# Ethernet_SD.net
KiCad netlist of a schematic drawn in Altium Designer
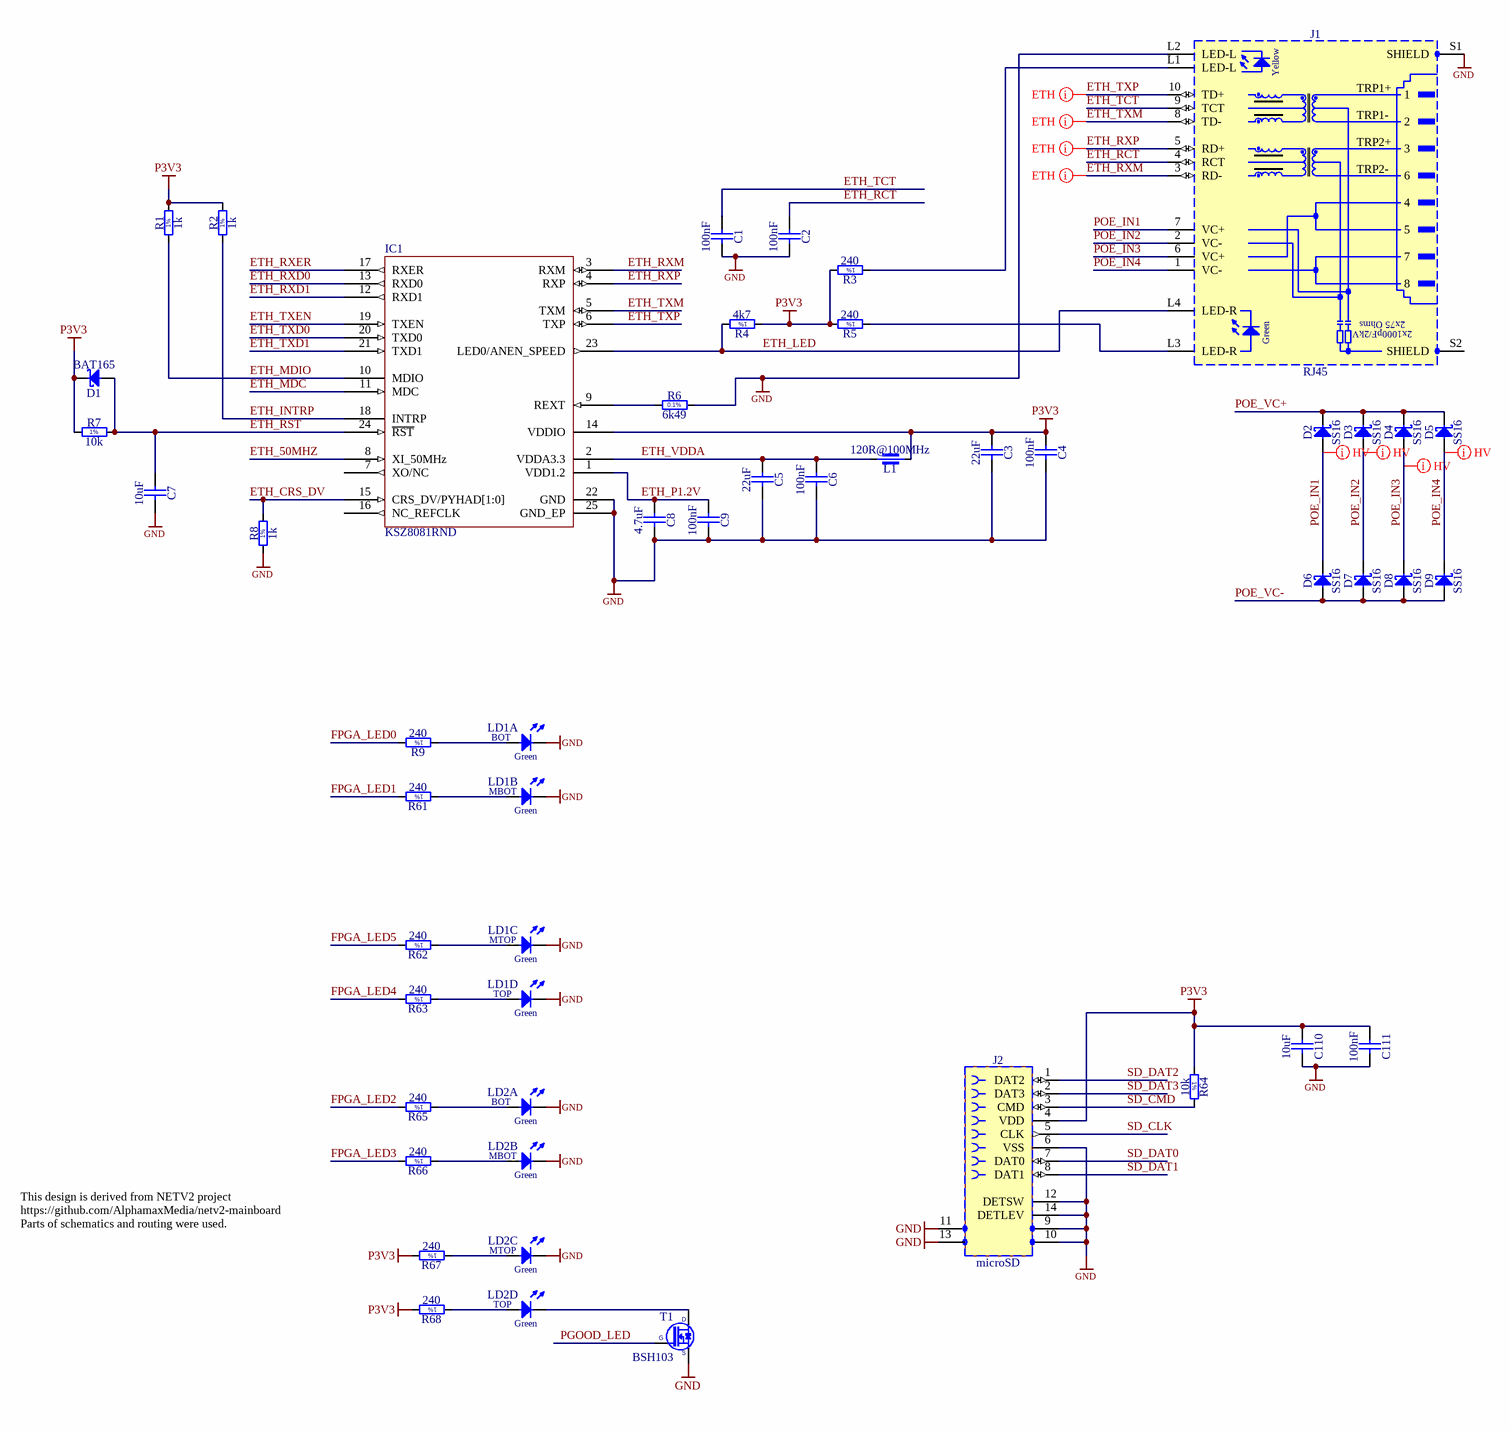
[diagram p0: Ethernet_SD.SchDoc]

(export (version "E")
  (design (tool "Eeschema 10.0.6"))
  (components
    (comp (ref "C1")
      (value "100nF")
      (footprint "CAPC2012X135N")
      (description "Non-polarised capacitor")
      (fields
        (field (name "PART NUMBER") "CC0805_100NF_50V_10%_X7R")
        (field (name "VOLTAGE") "50V")
        (field (name "AUTHOR") "CERN DEM JLC")
      )
      (libsource (lib "Capacitors") (part "Capacitor - non polarized"))
    )
    (comp (ref "C2")
      (value "100nF")
      (footprint "CAPC2012X135N")
      (description "Non-polarised capacitor")
      (fields
        (field (name "PART NUMBER") "CC0805_100NF_50V_10%_X7R")
        (field (name "VOLTAGE") "50V")
        (field (name "AUTHOR") "CERN DEM JLC")
      )
      (libsource (lib "Capacitors") (part "Capacitor - non polarized"))
    )
    (comp (ref "C3")
      (value "22uF")
      (footprint "CAPC2012X135N")
      (description "Non-polarised capacitor")
      (fields
        (field (name "PART NUMBER") "CC0805_22UF_16V_10%_X5R")
        (field (name "VOLTAGE") "16V")
        (field (name "AUTHOR") "CERN DEM JLC")
      )
      (libsource (lib "Capacitors") (part "Capacitor - non polarized"))
    )
    (comp (ref "C4")
      (value "100nF")
      (footprint "CAPC0603X33N")
      (description "Non-polarised capacitor")
      (fields
        (field (name "PART NUMBER") "CC0201_100NF_6.3V_10%_X5R")
        (field (name "VOLTAGE") "6.3V")
        (field (name "AUTHOR") "CERN DEM JLC")
      )
      (libsource (lib "Capacitors") (part "Capacitor - non polarized"))
    )
    (comp (ref "C5")
      (value "22uF")
      (footprint "CAPC2012X135N")
      (description "Non-polarised capacitor")
      (fields
        (field (name "PART NUMBER") "CC0805_22UF_16V_10%_X5R")
        (field (name "VOLTAGE") "16V")
        (field (name "AUTHOR") "CERN DEM JLC")
      )
      (libsource (lib "Capacitors") (part "Capacitor - non polarized"))
    )
    (comp (ref "C6")
      (value "100nF")
      (footprint "CAPC0603X33N")
      (description "Non-polarised capacitor")
      (fields
        (field (name "PART NUMBER") "CC0201_100NF_6.3V_10%_X5R")
        (field (name "VOLTAGE") "6.3V")
        (field (name "AUTHOR") "CERN DEM JLC")
      )
      (libsource (lib "Capacitors") (part "Capacitor - non polarized"))
    )
    (comp (ref "C7")
      (value "10uF")
      (footprint "CAPC1608X80N")
      (description "Non-polarised capacitor")
      (fields
        (field (name "PART NUMBER") "CC0603_10UF_10V_10%_X5R")
        (field (name "VOLTAGE") "10V")
        (field (name "AUTHOR") "CERN DEM JLC")
      )
      (libsource (lib "Capacitors") (part "Capacitor - non polarized"))
    )
    (comp (ref "C8")
      (value "4.7uF")
      (footprint "CAPC1005X55N")
      (description "Non-polarised capacitor")
      (fields
        (field (name "PART NUMBER") "CC0402_4.7UF_6.3V_20%_X5R")
        (field (name "VOLTAGE") "6.3V")
        (field (name "AUTHOR") "CERN DEM JLC")
      )
      (libsource (lib "Capacitors") (part "Capacitor - non polarized"))
    )
    (comp (ref "C9")
      (value "100nF")
      (footprint "CAPC0603X33N")
      (description "Non-polarised capacitor")
      (fields
        (field (name "PART NUMBER") "CC0201_100NF_6.3V_10%_X5R")
        (field (name "VOLTAGE") "6.3V")
        (field (name "AUTHOR") "CERN DEM JLC")
      )
      (libsource (lib "Capacitors") (part "Capacitor - non polarized"))
    )
    (comp (ref "C110")
      (value "10uF")
      (footprint "CAPC1608X80N")
      (description "Non-polarised capacitor")
      (fields
        (field (name "PART NUMBER") "CC0603_10UF_10V_10%_X5R")
        (field (name "VOLTAGE") "10V")
        (field (name "AUTHOR") "CERN DEM JLC")
      )
      (libsource (lib "Capacitors") (part "Capacitor - non polarized"))
    )
    (comp (ref "C111")
      (value "100nF")
      (footprint "CAPC0603X33N")
      (description "Non-polarised capacitor")
      (fields
        (field (name "PART NUMBER") "CC0201_100NF_6.3V_10%_X5R")
        (field (name "VOLTAGE") "6.3V")
        (field (name "AUTHOR") "CERN DEM JLC")
      )
      (libsource (lib "Capacitors") (part "Capacitor - non polarized"))
    )
    (comp (ref "D1")
      (value "BAT165")
      (footprint "SOD2512X110N")
      (description "Schottky Diode")
      (fields
        (field (name "VOLTAGE") "40V")
        (field (name "POWER") "750mA")
        (field (name "AUTHOR") "CERN DEM JLC")
      )
      (libsource (lib "ICs And Semiconductors") (part "Diode Schottky"))
    )
    (comp (ref "D2")
      (value "SS16")
      (footprint "DIOM5127X229N")
      (description "Schottky Diode")
      (fields
        (field (name "VOLTAGE") "60V")
        (field (name "POWER") "1A")
        (field (name "AUTHOR") "CERN DEM JLC")
      )
      (libsource (lib "ICs And Semiconductors") (part "Diode Schottky"))
    )
    (comp (ref "D3")
      (value "SS16")
      (footprint "DIOM5127X229N")
      (description "Schottky Diode")
      (fields
        (field (name "VOLTAGE") "60V")
        (field (name "POWER") "1A")
        (field (name "AUTHOR") "CERN DEM JLC")
      )
      (libsource (lib "ICs And Semiconductors") (part "Diode Schottky"))
    )
    (comp (ref "D4")
      (value "SS16")
      (footprint "DIOM5127X229N")
      (description "Schottky Diode")
      (fields
        (field (name "VOLTAGE") "60V")
        (field (name "POWER") "1A")
        (field (name "AUTHOR") "CERN DEM JLC")
      )
      (libsource (lib "ICs And Semiconductors") (part "Diode Schottky"))
    )
    (comp (ref "D5")
      (value "SS16")
      (footprint "DIOM5127X229N")
      (description "Schottky Diode")
      (fields
        (field (name "VOLTAGE") "60V")
        (field (name "POWER") "1A")
        (field (name "AUTHOR") "CERN DEM JLC")
      )
      (libsource (lib "ICs And Semiconductors") (part "Diode Schottky"))
    )
    (comp (ref "D6")
      (value "SS16")
      (footprint "DIOM5127X229N")
      (description "Schottky Diode")
      (fields
        (field (name "VOLTAGE") "60V")
        (field (name "POWER") "1A")
        (field (name "AUTHOR") "CERN DEM JLC")
      )
      (libsource (lib "ICs And Semiconductors") (part "Diode Schottky"))
    )
    (comp (ref "D7")
      (value "SS16")
      (footprint "DIOM5127X229N")
      (description "Schottky Diode")
      (fields
        (field (name "VOLTAGE") "60V")
        (field (name "POWER") "1A")
        (field (name "AUTHOR") "CERN DEM JLC")
      )
      (libsource (lib "ICs And Semiconductors") (part "Diode Schottky"))
    )
    (comp (ref "D8")
      (value "SS16")
      (footprint "DIOM5127X229N")
      (description "Schottky Diode")
      (fields
        (field (name "VOLTAGE") "60V")
        (field (name "POWER") "1A")
        (field (name "AUTHOR") "CERN DEM JLC")
      )
      (libsource (lib "ICs And Semiconductors") (part "Diode Schottky"))
    )
    (comp (ref "D9")
      (value "SS16")
      (footprint "DIOM5127X229N")
      (description "Schottky Diode")
      (fields
        (field (name "VOLTAGE") "60V")
        (field (name "POWER") "1A")
        (field (name "AUTHOR") "CERN DEM JLC")
      )
      (libsource (lib "ICs And Semiconductors") (part "Diode Schottky"))
    )
    (comp (ref "IC1")
      (value "KSZ8081RND")
      (footprint "QFN50P400X400-24VBN")
      (description "KSZ8081RND MII Ethernet PHY")
      (fields (field (name "MPN") "KSZ8081RNDCA"))
      (libsource (lib "commonsch-new") (part "KSZ8081RND"))
    )
    (comp (ref "J1")
      (value "RJ45")
      (footprint "ABRACON_ARJM11C7-114-BA-EW2")
      (description "MagJack 10/100BaseT, PoE+, 1X1, OG/Y, -40 to 85*C, Tab Up, RoHS")
      (fields
        (field (name "PART NUMBER") "ARJM11C7-114-BA-EW2")
        (field (name "MANUFACTURER") "Abracon")
        (field (name "AUTHOR") "GK")
      )
      (libsource (lib "LIBRARY_SCH") (part "CON_ETH_POE_ARJM11C7"))
    )
    (comp (ref "J2")
      (value "microSD")
      (footprint "MOLEX_502570-0893")
      (description "Connector MicroSD 8 Pin")
      (fields
        (field (name "PART NUMBER") "MOLEX_502570-0893")
        (field (name "MANUFACTURER") "MOLEX")
        (field (name "AUTHOR") "CERN DEM JLC")
      )
      (libsource (lib "Connectors") (part "MOLEX_502570-0893"))
    )
    (comp (ref "L1")
      (value "120R@100MHz")
      (footprint "INDC1608X65N")
      (fields
        (field (name "PART NUMBER") "IND0603_MURATA_BLM18SG121TN1D")
        (field (name "POWER") "3A")
        (field (name "TOLERANCE") "±25%")
        (field (name "AUTHOR") "CERN DEM JLC")
      )
      (libsource (lib "Inductors & Transformers") (part "Ferrite Bead"))
    )
    (comp (ref "LD1")
      (value "Green")
      (footprint "LED_BIVAR_H485CGDL")
      (description "LED x4 Green 1C2A-BOT_3C4A_5C6A_7C8A-TOP")
      (fields
        (field (name "PART NUMBER") "LED_BIVAR_H485CGDL")
        (field (name "MANUFACTURER") "BIVAR")
        (field (name "AUTHOR") "CERN DEM JLC")
      )
      (libsource (lib "ICs And Semiconductors") (part "LED x4 Green 1C2A-BOT_3C4A_5C6A_7C8A-TOP"))
    )
    (comp (ref "LD2")
      (value "Green")
      (footprint "LED_BIVAR_H485CGDL")
      (description "LED x4 Green 1C2A-BOT_3C4A_5C6A_7C8A-TOP")
      (fields
        (field (name "PART NUMBER") "LED_BIVAR_H485CGDL")
        (field (name "MANUFACTURER") "BIVAR")
        (field (name "AUTHOR") "CERN DEM JLC")
      )
      (libsource (lib "ICs And Semiconductors") (part "LED x4 Green 1C2A-BOT_3C4A_5C6A_7C8A-TOP"))
    )
    (comp (ref "R1")
      (value "1k")
      (footprint "RESC1005X40N")
      (description "Resistor - 1%")
      (fields
        (field (name "PART NUMBER") "R0402_1K_1%_0.0625W_100PPM")
        (field (name "POWER") "0.0625W")
        (field (name "AUTHOR") "CERN DEM JLC")
      )
      (libsource (lib "Resistors") (part "Resistor - 1%"))
    )
    (comp (ref "R2")
      (value "1k")
      (footprint "RESC1005X40N")
      (description "Resistor - 1%")
      (fields
        (field (name "PART NUMBER") "R0402_1K_1%_0.0625W_100PPM")
        (field (name "POWER") "0.0625W")
        (field (name "AUTHOR") "CERN DEM JLC")
      )
      (libsource (lib "Resistors") (part "Resistor - 1%"))
    )
    (comp (ref "R3")
      (value "240")
      (footprint "RESC1005X40N")
      (description "Resistor - 1%")
      (fields
        (field (name "PART NUMBER") "R0402_240R_1%_0.0625W_100PPM")
        (field (name "POWER") "0.0625W")
        (field (name "AUTHOR") "CERN DEM JLC")
      )
      (libsource (lib "Resistors") (part "Resistor - 1%"))
    )
    (comp (ref "R4")
      (value "4k7")
      (footprint "RESC1005X40N")
      (description "Resistor - 1%")
      (fields
        (field (name "PART NUMBER") "R0402_4K7_1%_0.0625W_100PPM")
        (field (name "POWER") "0.0625W")
        (field (name "AUTHOR") "CERN DEM JLC")
      )
      (libsource (lib "Resistors") (part "Resistor - 1%"))
    )
    (comp (ref "R5")
      (value "240")
      (footprint "RESC1005X40N")
      (description "Resistor - 1%")
      (fields
        (field (name "PART NUMBER") "R0402_240R_1%_0.0625W_100PPM")
        (field (name "POWER") "0.0625W")
        (field (name "AUTHOR") "CERN DEM JLC")
      )
      (libsource (lib "Resistors") (part "Resistor - 1%"))
    )
    (comp (ref "R6")
      (value "6k49")
      (footprint "RESC1005X35N")
      (description "Resistor - 0.1%")
      (fields
        (field (name "PART NUMBER") "R0402_6K49_0.1%_0.063W_25PPM")
        (field (name "POWER") "0.063W")
        (field (name "AUTHOR") "CERN DEM JMW")
      )
      (libsource (lib "Resistors") (part "Resistor - 0.1%"))
    )
    (comp (ref "R7")
      (value "10k")
      (footprint "RESC1005X40N")
      (description "Resistor - 1%")
      (fields
        (field (name "PART NUMBER") "R0402_10K_1%_0.0625W_100PPM")
        (field (name "POWER") "0.0625W")
        (field (name "AUTHOR") "CERN DEM JLC")
      )
      (libsource (lib "Resistors") (part "Resistor - 1%"))
    )
    (comp (ref "R8")
      (value "1k")
      (footprint "RESC1005X40N")
      (description "Resistor - 1%")
      (fields
        (field (name "PART NUMBER") "R0402_1K_1%_0.0625W_100PPM")
        (field (name "POWER") "0.0625W")
        (field (name "AUTHOR") "CERN DEM JLC")
      )
      (libsource (lib "Resistors") (part "Resistor - 1%"))
    )
    (comp (ref "R9")
      (value "240")
      (footprint "RESC1005X40N")
      (description "Resistor - 1%")
      (fields
        (field (name "PART NUMBER") "R0402_240R_1%_0.0625W_100PPM")
        (field (name "POWER") "0.0625W")
        (field (name "AUTHOR") "CERN DEM JLC")
      )
      (libsource (lib "Resistors") (part "Resistor - 1%"))
    )
    (comp (ref "R61")
      (value "240")
      (footprint "RESC1005X40N")
      (description "Resistor - 1%")
      (fields
        (field (name "PART NUMBER") "R0402_240R_1%_0.0625W_100PPM")
        (field (name "POWER") "0.0625W")
        (field (name "AUTHOR") "CERN DEM JLC")
      )
      (libsource (lib "Resistors") (part "Resistor - 1%"))
    )
    (comp (ref "R62")
      (value "240")
      (footprint "RESC1005X40N")
      (description "Resistor - 1%")
      (fields
        (field (name "PART NUMBER") "R0402_240R_1%_0.0625W_100PPM")
        (field (name "POWER") "0.0625W")
        (field (name "AUTHOR") "CERN DEM JLC")
      )
      (libsource (lib "Resistors") (part "Resistor - 1%"))
    )
    (comp (ref "R63")
      (value "240")
      (footprint "RESC1005X40N")
      (description "Resistor - 1%")
      (fields
        (field (name "PART NUMBER") "R0402_240R_1%_0.0625W_100PPM")
        (field (name "POWER") "0.0625W")
        (field (name "AUTHOR") "CERN DEM JLC")
      )
      (libsource (lib "Resistors") (part "Resistor - 1%"))
    )
    (comp (ref "R64")
      (value "10k")
      (footprint "RESC1005X40N")
      (description "Resistor - 1%")
      (fields
        (field (name "PART NUMBER") "R0402_10K_1%_0.0625W_100PPM")
        (field (name "POWER") "0.0625W")
        (field (name "AUTHOR") "CERN DEM JLC")
      )
      (libsource (lib "Resistors") (part "Resistor - 1%"))
    )
    (comp (ref "R65")
      (value "240")
      (footprint "RESC1005X40N")
      (description "Resistor - 1%")
      (fields
        (field (name "PART NUMBER") "R0402_240R_1%_0.0625W_100PPM")
        (field (name "POWER") "0.0625W")
        (field (name "AUTHOR") "CERN DEM JLC")
      )
      (libsource (lib "Resistors") (part "Resistor - 1%"))
    )
    (comp (ref "R66")
      (value "240")
      (footprint "RESC1005X40N")
      (description "Resistor - 1%")
      (fields
        (field (name "PART NUMBER") "R0402_240R_1%_0.0625W_100PPM")
        (field (name "POWER") "0.0625W")
        (field (name "AUTHOR") "CERN DEM JLC")
      )
      (libsource (lib "Resistors") (part "Resistor - 1%"))
    )
    (comp (ref "R67")
      (value "240")
      (footprint "RESC1005X40N")
      (description "Resistor - 1%")
      (fields
        (field (name "PART NUMBER") "R0402_240R_1%_0.0625W_100PPM")
        (field (name "POWER") "0.0625W")
        (field (name "AUTHOR") "CERN DEM JLC")
      )
      (libsource (lib "Resistors") (part "Resistor - 1%"))
    )
    (comp (ref "R68")
      (value "240")
      (footprint "RESC1005X40N")
      (description "Resistor - 1%")
      (fields
        (field (name "PART NUMBER") "R0402_240R_1%_0.0625W_100PPM")
        (field (name "POWER") "0.0625W")
        (field (name "AUTHOR") "CERN DEM JLC")
      )
      (libsource (lib "Resistors") (part "Resistor - 1%"))
    )
    (comp (ref "T1")
      (value "BSH103")
      (footprint "SOT95P230X110-3N")
      (description "N-CHANNEL MOSFET WITH DIODE")
      (fields (field (name "MANUFACTURER") "NEXPERIA") (field (name "AUTHOR") "CERN DEM JLC"))
      (libsource (lib "ICs And Semiconductors") (part "N-MOSFET-D 1G 2S 3D"))
    )
  )
  (nets
    (net (code "1") (name "/ETH_50MHZ") (class "Default")
      (node (ref "IC1") (pin "8") (pinfunction "XI_50MHz_8") (pintype "input"))
    )
    (net (code "2") (name "/ETH_CRS_DV") (class "Default")
      (node (ref "IC1") (pin "15") (pinfunction "CRS_DV/PYHAD[1:0]_15") (pintype "input"))
      (node (ref "R8") (pin "2") (pinfunction "2_2") (pintype "passive"))
    )
    (net (code "3") (name "/ETH_INTRP") (class "Default")
      (node (ref "IC1") (pin "18") (pinfunction "INTRP_18") (pintype "open_collector"))
      (node (ref "R2") (pin "1") (pinfunction "1_1") (pintype "passive"))
    )
    (net (code "4") (name "/ETH_LED") (class "Default")
      (node (ref "IC1") (pin "23") (pinfunction "LED0/ANEN_SPEED_23") (pintype "output"))
      (node (ref "J1") (pin "L4") (pinfunction "LED-R_L4") (pintype "passive"))
      (node (ref "R4") (pin "2") (pinfunction "2_2") (pintype "passive"))
    )
    (net (code "5") (name "/ETH_MDC") (class "Default")
      (node (ref "IC1") (pin "11") (pinfunction "MDC_11") (pintype "input"))
    )
    (net (code "6") (name "/ETH_MDIO") (class "Default")
      (node (ref "IC1") (pin "10") (pinfunction "MDIO_10") (pintype "open_collector"))
      (node (ref "R1") (pin "1") (pinfunction "1_1") (pintype "passive"))
    )
    (net (code "7") (name "/ETH_P1.2V") (class "Default")
      (node (ref "C8") (pin "1") (pinfunction "1_1") (pintype "passive"))
      (node (ref "C9") (pin "1") (pinfunction "1_1") (pintype "passive"))
      (node (ref "IC1") (pin "1") (pinfunction "VDD1.2_1") (pintype "power_in"))
    )
    (net (code "8") (name "/ETH_RCT") (class "Default")
      (node (ref "C2") (pin "1") (pinfunction "1_1") (pintype "passive"))
      (node (ref "J1") (pin "4") (pinfunction "RCT_4") (pintype "bidirectional"))
    )
    (net (code "9") (name "/ETH_RST") (class "Default")
      (node (ref "C7") (pin "1") (pinfunction "1_1") (pintype "passive"))
      (node (ref "D1") (pin "2") (pinfunction "A_2") (pintype "passive"))
      (node (ref "IC1") (pin "24") (pinfunction "~{RST}_24") (pintype "input"))
      (node (ref "R7") (pin "2") (pinfunction "2_2") (pintype "passive"))
    )
    (net (code "10") (name "/ETH_RXD0") (class "Default")
      (node (ref "IC1") (pin "13") (pinfunction "RXD0_13") (pintype "output"))
    )
    (net (code "11") (name "/ETH_RXD1") (class "Default")
      (node (ref "IC1") (pin "12") (pinfunction "RXD1_12") (pintype "output"))
    )
    (net (code "12") (name "/ETH_RXER") (class "Default")
      (node (ref "IC1") (pin "17") (pinfunction "RXER_17") (pintype "output"))
    )
    (net (code "13") (name "/ETH_RXM") (class "Default")
      (node (ref "IC1") (pin "3") (pinfunction "RXM_3") (pintype "bidirectional"))
      (node (ref "J1") (pin "3") (pinfunction "RD-_3") (pintype "bidirectional"))
    )
    (net (code "14") (name "/ETH_RXP") (class "Default")
      (node (ref "IC1") (pin "4") (pinfunction "RXP_4") (pintype "bidirectional"))
      (node (ref "J1") (pin "5") (pinfunction "RD+_5") (pintype "bidirectional"))
    )
    (net (code "15") (name "/ETH_TCT") (class "Default")
      (node (ref "C1") (pin "1") (pinfunction "1_1") (pintype "passive"))
      (node (ref "J1") (pin "9") (pinfunction "TCT_9") (pintype "bidirectional"))
    )
    (net (code "16") (name "/ETH_TXD0") (class "Default")
      (node (ref "IC1") (pin "20") (pinfunction "TXD0_20") (pintype "input"))
    )
    (net (code "17") (name "/ETH_TXD1") (class "Default")
      (node (ref "IC1") (pin "21") (pinfunction "TXD1_21") (pintype "input"))
    )
    (net (code "18") (name "/ETH_TXEN") (class "Default")
      (node (ref "IC1") (pin "19") (pinfunction "TXEN_19") (pintype "input"))
    )
    (net (code "19") (name "/ETH_TXM") (class "Default")
      (node (ref "IC1") (pin "5") (pinfunction "TXM_5") (pintype "bidirectional"))
      (node (ref "J1") (pin "8") (pinfunction "TD-_8") (pintype "bidirectional"))
    )
    (net (code "20") (name "/ETH_TXP") (class "Default")
      (node (ref "IC1") (pin "6") (pinfunction "TXP_6") (pintype "bidirectional"))
      (node (ref "J1") (pin "10") (pinfunction "TD+_10") (pintype "bidirectional"))
    )
    (net (code "21") (name "/ETH_VDDA") (class "Default")
      (node (ref "C5") (pin "1") (pinfunction "1_1") (pintype "passive"))
      (node (ref "C6") (pin "1") (pinfunction "1_1") (pintype "passive"))
      (node (ref "IC1") (pin "2") (pinfunction "VDDA3.3_2") (pintype "power_in"))
      (node (ref "L1") (pin "2") (pinfunction "2_2") (pintype "passive"))
    )
    (net (code "22") (name "/FPGA_LED0") (class "Default")
      (node (ref "R9") (pin "2") (pinfunction "2_2") (pintype "passive"))
    )
    (net (code "23") (name "/FPGA_LED1") (class "Default")
      (node (ref "R61") (pin "2") (pinfunction "2_2") (pintype "passive"))
    )
    (net (code "24") (name "/FPGA_LED2") (class "Default")
      (node (ref "R65") (pin "2") (pinfunction "2_2") (pintype "passive"))
    )
    (net (code "25") (name "/FPGA_LED3") (class "Default")
      (node (ref "R66") (pin "2") (pinfunction "2_2") (pintype "passive"))
    )
    (net (code "26") (name "/FPGA_LED4") (class "Default")
      (node (ref "R63") (pin "2") (pinfunction "2_2") (pintype "passive"))
    )
    (net (code "27") (name "/FPGA_LED5") (class "Default")
      (node (ref "R62") (pin "2") (pinfunction "2_2") (pintype "passive"))
    )
    (net (code "28") (name "/PGOOD_LED") (class "Default")
      (node (ref "T1") (pin "1") (pinfunction "G_1") (pintype "passive"))
    )
    (net (code "29") (name "/POE_IN1") (class "Default")
      (node (ref "D2") (pin "2") (pinfunction "A_2") (pintype "passive"))
      (node (ref "D6") (pin "1") (pinfunction "C_1") (pintype "passive"))
      (node (ref "J1") (pin "7") (pinfunction "VC+_7") (pintype "passive"))
    )
    (net (code "30") (name "/POE_IN2") (class "Default")
      (node (ref "D3") (pin "2") (pinfunction "A_2") (pintype "passive"))
      (node (ref "D7") (pin "1") (pinfunction "C_1") (pintype "passive"))
      (node (ref "J1") (pin "2") (pinfunction "VC-_2") (pintype "passive"))
    )
    (net (code "31") (name "/POE_IN3") (class "Default")
      (node (ref "D4") (pin "2") (pinfunction "A_2") (pintype "passive"))
      (node (ref "D8") (pin "1") (pinfunction "C_1") (pintype "passive"))
      (node (ref "J1") (pin "6") (pinfunction "VC+_6") (pintype "passive"))
    )
    (net (code "32") (name "/POE_IN4") (class "Default")
      (node (ref "D5") (pin "2") (pinfunction "A_2") (pintype "passive"))
      (node (ref "D9") (pin "1") (pinfunction "C_1") (pintype "passive"))
      (node (ref "J1") (pin "1") (pinfunction "VC-_1") (pintype "passive"))
    )
    (net (code "33") (name "/POE_VC+") (class "Default")
      (node (ref "D2") (pin "1") (pinfunction "C_1") (pintype "passive"))
      (node (ref "D3") (pin "1") (pinfunction "C_1") (pintype "passive"))
      (node (ref "D4") (pin "1") (pinfunction "C_1") (pintype "passive"))
      (node (ref "D5") (pin "1") (pinfunction "C_1") (pintype "passive"))
    )
    (net (code "34") (name "/POE_VC-") (class "Default")
      (node (ref "D6") (pin "2") (pinfunction "A_2") (pintype "passive"))
      (node (ref "D7") (pin "2") (pinfunction "A_2") (pintype "passive"))
      (node (ref "D8") (pin "2") (pinfunction "A_2") (pintype "passive"))
      (node (ref "D9") (pin "2") (pinfunction "A_2") (pintype "passive"))
    )
    (net (code "35") (name "/SD_CLK") (class "Default")
      (node (ref "J2") (pin "5") (pinfunction "CLK_5") (pintype "output"))
    )
    (net (code "36") (name "/SD_CMD") (class "Default")
      (node (ref "J2") (pin "3") (pinfunction "CMD_3") (pintype "bidirectional"))
      (node (ref "R64") (pin "2") (pinfunction "2_2") (pintype "passive"))
    )
    (net (code "37") (name "/SD_DAT0") (class "Default")
      (node (ref "J2") (pin "7") (pinfunction "DAT0_7") (pintype "bidirectional"))
    )
    (net (code "38") (name "/SD_DAT1") (class "Default")
      (node (ref "J2") (pin "8") (pinfunction "DAT1_8") (pintype "bidirectional"))
    )
    (net (code "39") (name "/SD_DAT2") (class "Default")
      (node (ref "J2") (pin "1") (pinfunction "DAT2_1") (pintype "bidirectional"))
    )
    (net (code "40") (name "/SD_DAT3") (class "Default")
      (node (ref "J2") (pin "2") (pinfunction "DAT3_2") (pintype "bidirectional"))
    )
    (net (code "41") (name "GND") (class "Default")
      (node (ref "C1") (pin "2") (pinfunction "2_2") (pintype "passive"))
      (node (ref "C110") (pin "2") (pinfunction "2_2") (pintype "passive"))
      (node (ref "C111") (pin "2") (pinfunction "2_2") (pintype "passive"))
      (node (ref "C2") (pin "2") (pinfunction "2_2") (pintype "passive"))
      (node (ref "C3") (pin "2") (pinfunction "2_2") (pintype "passive"))
      (node (ref "C4") (pin "2") (pinfunction "2_2") (pintype "passive"))
      (node (ref "C5") (pin "2") (pinfunction "2_2") (pintype "passive"))
      (node (ref "C6") (pin "2") (pinfunction "2_2") (pintype "passive"))
      (node (ref "C7") (pin "2") (pinfunction "2_2") (pintype "passive"))
      (node (ref "C8") (pin "2") (pinfunction "2_2") (pintype "passive"))
      (node (ref "C9") (pin "2") (pinfunction "2_2") (pintype "passive"))
      (node (ref "IC1") (pin "22") (pinfunction "GND_22") (pintype "power_in"))
      (node (ref "IC1") (pin "25") (pinfunction "GND_EP_25") (pintype "power_in"))
      (node (ref "J1") (pin "L2") (pinfunction "LED-L_L2") (pintype "passive"))
      (node (ref "J1") (pin "S1") (pinfunction "SHIELD_S1") (pintype "power_in"))
      (node (ref "J2") (pin "10") (pinfunction "10_10") (pintype "passive"))
      (node (ref "J2") (pin "11") (pinfunction "11_11") (pintype "passive"))
      (node (ref "J2") (pin "12") (pinfunction "DETSW_12") (pintype "passive"))
      (node (ref "J2") (pin "13") (pinfunction "13_13") (pintype "passive"))
      (node (ref "J2") (pin "14") (pinfunction "DETLEV_14") (pintype "passive"))
      (node (ref "J2") (pin "6") (pinfunction "VSS_6") (pintype "power_in"))
      (node (ref "J2") (pin "9") (pinfunction "9_9") (pintype "passive"))
      (node (ref "LD1") (pin "1") (pinfunction "C_1") (pintype "passive"))
      (node (ref "LD1") (pin "3") (pinfunction "C_3") (pintype "passive"))
      (node (ref "LD1") (pin "5") (pinfunction "C_5") (pintype "passive"))
      (node (ref "LD1") (pin "7") (pinfunction "C_7") (pintype "passive"))
      (node (ref "LD2") (pin "1") (pinfunction "C_1") (pintype "passive"))
      (node (ref "LD2") (pin "3") (pinfunction "C_3") (pintype "passive"))
      (node (ref "LD2") (pin "5") (pinfunction "C_5") (pintype "passive"))
      (node (ref "R6") (pin "2") (pinfunction "2_2") (pintype "passive"))
      (node (ref "R8") (pin "1") (pinfunction "1_1") (pintype "passive"))
      (node (ref "T1") (pin "2") (pinfunction "S_2") (pintype "passive"))
    )
    (net (code "42") (name "Net-(IC1-REXT)") (class "Default")
      (node (ref "IC1") (pin "9") (pinfunction "REXT_9") (pintype "input"))
      (node (ref "R6") (pin "1") (pinfunction "1_1") (pintype "passive"))
    )
    (net (code "43") (name "Net-(J1-LED-L-PadL1)") (class "Default")
      (node (ref "J1") (pin "L1") (pinfunction "LED-L_L1") (pintype "passive"))
      (node (ref "R3") (pin "1") (pinfunction "1_1") (pintype "passive"))
    )
    (net (code "44") (name "Net-(J1-LED-R-PadL3)") (class "Default")
      (node (ref "J1") (pin "L3") (pinfunction "LED-R_L3") (pintype "passive"))
      (node (ref "R5") (pin "1") (pinfunction "1_1") (pintype "passive"))
    )
    (net (code "45") (name "Net-(LD1A-A)") (class "Default")
      (node (ref "LD1") (pin "2") (pinfunction "A_2") (pintype "passive"))
      (node (ref "R9") (pin "1") (pinfunction "1_1") (pintype "passive"))
    )
    (net (code "46") (name "Net-(LD1B-A)") (class "Default")
      (node (ref "LD1") (pin "4") (pinfunction "A_4") (pintype "passive"))
      (node (ref "R61") (pin "1") (pinfunction "1_1") (pintype "passive"))
    )
    (net (code "47") (name "Net-(LD1C-A)") (class "Default")
      (node (ref "LD1") (pin "6") (pinfunction "A_6") (pintype "passive"))
      (node (ref "R62") (pin "1") (pinfunction "1_1") (pintype "passive"))
    )
    (net (code "48") (name "Net-(LD1D-A)") (class "Default")
      (node (ref "LD1") (pin "8") (pinfunction "A_8") (pintype "passive"))
      (node (ref "R63") (pin "1") (pinfunction "1_1") (pintype "passive"))
    )
    (net (code "49") (name "Net-(LD2A-A)") (class "Default")
      (node (ref "LD2") (pin "2") (pinfunction "A_2") (pintype "passive"))
      (node (ref "R65") (pin "1") (pinfunction "1_1") (pintype "passive"))
    )
    (net (code "50") (name "Net-(LD2B-A)") (class "Default")
      (node (ref "LD2") (pin "4") (pinfunction "A_4") (pintype "passive"))
      (node (ref "R66") (pin "1") (pinfunction "1_1") (pintype "passive"))
    )
    (net (code "51") (name "Net-(LD2C-A)") (class "Default")
      (node (ref "LD2") (pin "6") (pinfunction "A_6") (pintype "passive"))
      (node (ref "R67") (pin "1") (pinfunction "1_1") (pintype "passive"))
    )
    (net (code "52") (name "Net-(LD2D-A)") (class "Default")
      (node (ref "LD2") (pin "8") (pinfunction "A_8") (pintype "passive"))
      (node (ref "R68") (pin "1") (pinfunction "1_1") (pintype "passive"))
    )
    (net (code "53") (name "Net-(LD2D-C)") (class "Default")
      (node (ref "LD2") (pin "7") (pinfunction "C_7") (pintype "passive"))
      (node (ref "T1") (pin "3") (pinfunction "D_3") (pintype "passive"))
    )
    (net (code "54") (name "P3V3") (class "Default")
      (node (ref "C110") (pin "1") (pinfunction "1_1") (pintype "passive"))
      (node (ref "C111") (pin "1") (pinfunction "1_1") (pintype "passive"))
      (node (ref "C3") (pin "1") (pinfunction "1_1") (pintype "passive"))
      (node (ref "C4") (pin "1") (pinfunction "1_1") (pintype "passive"))
      (node (ref "D1") (pin "1") (pinfunction "C_1") (pintype "passive"))
      (node (ref "IC1") (pin "14") (pinfunction "VDDIO_14") (pintype "power_in"))
      (node (ref "J2") (pin "4") (pinfunction "VDD_4") (pintype "power_in"))
      (node (ref "L1") (pin "1") (pinfunction "1_1") (pintype "passive"))
      (node (ref "R1") (pin "2") (pinfunction "2_2") (pintype "passive"))
      (node (ref "R2") (pin "2") (pinfunction "2_2") (pintype "passive"))
      (node (ref "R3") (pin "2") (pinfunction "2_2") (pintype "passive"))
      (node (ref "R4") (pin "1") (pinfunction "1_1") (pintype "passive"))
      (node (ref "R5") (pin "2") (pinfunction "2_2") (pintype "passive"))
      (node (ref "R64") (pin "1") (pinfunction "1_1") (pintype "passive"))
      (node (ref "R67") (pin "2") (pinfunction "2_2") (pintype "passive"))
      (node (ref "R68") (pin "2") (pinfunction "2_2") (pintype "passive"))
      (node (ref "R7") (pin "1") (pinfunction "1_1") (pintype "passive"))
    )
    (net (code "55") (name "unconnected-(IC1-NC_REFCLK-Pad16)") (class "Default")
      (node (ref "IC1") (pin "16") (pinfunction "NC_REFCLK_16") (pintype "output"))
    )
    (net (code "56") (name "unconnected-(IC1-XO{slash}NC-Pad7)") (class "Default")
      (node (ref "IC1") (pin "7") (pinfunction "XO/NC_7") (pintype "output"))
    )
    (net (code "57") (name "unconnected-(J1-SHIELD-PadS2)") (class "Default")
      (node (ref "J1") (pin "S2") (pinfunction "SHIELD_S2") (pintype "power_in"))
    )
  )
)
